# HD-JYQ70-YD03-POWER.net
KiCad netlist of a schematic drawn in Altium Designer
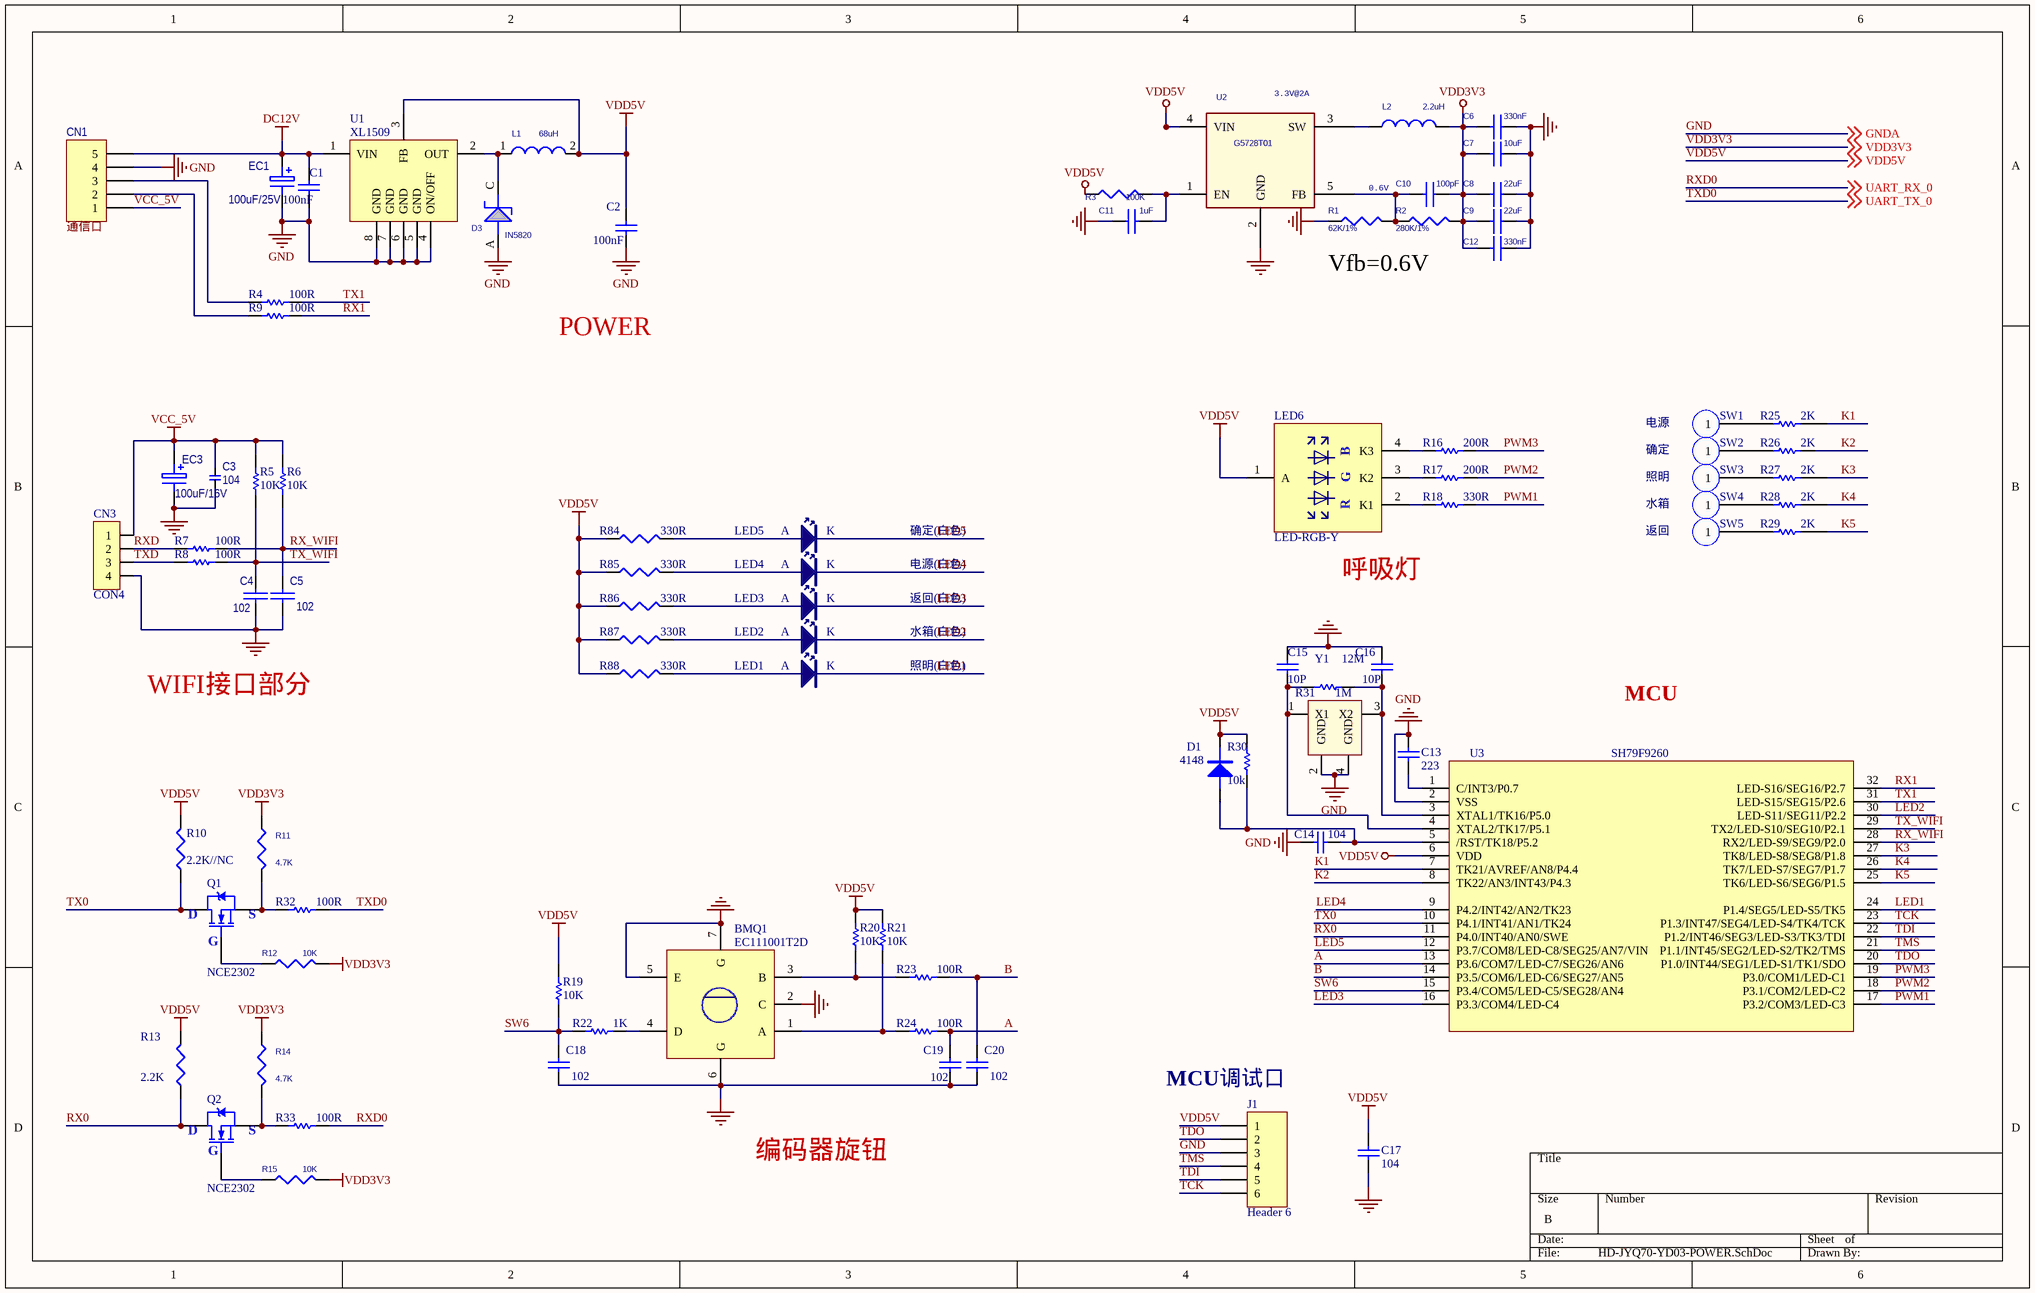
[diagram p0: HD-JYQ70-YD03-POWER.SchDoc]

(export (version "E")
  (design (tool "Eeschema 10.0.6"))
  (components
    (comp (ref "BMQ1")
      (value "EC111001T2D")
      (footprint "EC111001T2D")
      (libsource (lib "DHX") (part "EC111001T2D"))
    )
    (comp (ref "C1")
      (value "100nF")
      (footprint "X-0603C")
      (description "Capacitor (Semiconductor SIM Model)")
      (fields (field (name "Comment") "Cap Semi") (field (name "PUBLISHER") "Altium Limited"))
      (libsource (lib "Miscellaneous Devices") (part "Cap Semi"))
    )
    (comp (ref "C2")
      (value "100nF")
      (footprint "X-0603C")
      (description "Capacitor (Semiconductor SIM Model)")
      (fields (field (name "Comment") "Cap Semi") (field (name "PUBLISHER") "Altium Limited"))
      (libsource (lib "Miscellaneous Devices") (part "Cap Semi"))
    )
    (comp (ref "C3")
      (value "104")
      (footprint "X-0603C")
      (description "贴片电容")
      (libsource (lib "*") (part "C1"))
    )
    (comp (ref "C4")
      (value "102")
      (footprint "X-0603C")
      (description "贴片电容")
      (libsource (lib "*") (part "CAP1"))
    )
    (comp (ref "C5")
      (value "102")
      (footprint "X-0603C")
      (description "贴片电容")
      (libsource (lib "*") (part "CAP1"))
    )
    (comp (ref "C6")
      (value "330nF")
      (footprint "X-0603C")
      (fields (field (name "VOLTAGE") "X5R/10V"))
      (libsource (lib "*") (part "CAP NP_0"))
    )
    (comp (ref "C7")
      (value "10uF")
      (footprint "X-0805C")
      (fields (field (name "VOLTAGE") "X5R/6.3V"))
      (libsource (lib "*") (part "CAP NP"))
    )
    (comp (ref "C8")
      (value "22uF")
      (footprint "X-0805C")
      (fields (field (name "VOLTAGE") "X5R/6.3V"))
      (libsource (lib "*") (part "CAP NP"))
    )
    (comp (ref "C9")
      (value "22uF")
      (footprint "X-0805C")
      (fields (field (name "VOLTAGE") "X5R/6.3V"))
      (libsource (lib "*") (part "CAP NP"))
    )
    (comp (ref "C10")
      (value "100pF")
      (footprint "X-0603C")
      (fields (field (name "VOLTAGE") "COG/5V"))
      (libsource (lib "*") (part "CAP NP"))
    )
    (comp (ref "C11")
      (value "1uF")
      (footprint "X-0603C")
      (fields (field (name "VOLTAGE") "X5R/10V"))
      (libsource (lib "*") (part "CAP NP_0"))
    )
    (comp (ref "C12")
      (value "330nF")
      (footprint "X-0805C")
      (fields (field (name "VOLTAGE") "X5R/10V"))
      (libsource (lib "*") (part "CAP NP"))
    )
    (comp (ref "C13")
      (value "223")
      (footprint "X-0603C")
      (description "Capacitor")
      (fields (field (name "Comment") "Cap") (field (name "PUBLISHER") "Altium Limited"))
      (libsource (lib "Miscellaneous Devices") (part "Cap"))
    )
    (comp (ref "C14")
      (value "104")
      (footprint "X-0603C")
      (description "Capacitor")
      (fields (field (name "Comment") "Cap") (field (name "PUBLISHER") "Altium Limited"))
      (libsource (lib "Miscellaneous Devices") (part "Cap"))
    )
    (comp (ref "C15")
      (value "10P")
      (footprint "X-0603C")
      (description "Capacitor")
      (fields (field (name "Comment") "Cap") (field (name "PUBLISHER") "Altium Limited"))
      (libsource (lib "Miscellaneous Devices") (part "Cap"))
    )
    (comp (ref "C16")
      (value "10P")
      (footprint "X-0603C")
      (description "Capacitor")
      (fields (field (name "Comment") "Cap") (field (name "PUBLISHER") "Altium Limited"))
      (libsource (lib "Miscellaneous Devices") (part "Cap"))
    )
    (comp (ref "C17")
      (value "104")
      (footprint "X-0603C")
      (description "Capacitor")
      (fields (field (name "Comment") "Cap") (field (name "PUBLISHER") "Altium Limited"))
      (libsource (lib "Miscellaneous Devices") (part "Cap"))
    )
    (comp (ref "C18")
      (value "102")
      (footprint "X-0603C")
      (description "Capacitor")
      (fields (field (name "Comment") "Cap") (field (name "PUBLISHER") "Altium Limited"))
      (libsource (lib "Miscellaneous Devices") (part "Cap"))
    )
    (comp (ref "C19")
      (value "102")
      (footprint "X-0603C")
      (description "Capacitor")
      (fields (field (name "Comment") "Cap") (field (name "PUBLISHER") "Altium Limited"))
      (libsource (lib "Miscellaneous Devices") (part "Cap"))
    )
    (comp (ref "C20")
      (value "102")
      (footprint "X-0603C")
      (description "Capacitor")
      (fields (field (name "Comment") "Cap") (field (name "PUBLISHER") "Altium Limited"))
      (libsource (lib "Miscellaneous Devices") (part "Cap"))
    )
    (comp (ref "CN1")
      (value "通信口")
      (footprint "JC25-5Y")
      (description "孔座")
      (fields (field (name "PUBLISHER") "Altium Limited"))
      (libsource (lib "Miscellaneous Connectors") (part "Header 5"))
    )
    (comp (ref "CN3")
      (value "CON4")
      (footprint "CoN-JC25-4Y")
      (description "Connector")
      (libsource (lib "Stander PCB lib_V1.2(20170627)") (part "CON4"))
    )
    (comp (ref "D1") (value "4148") (footprint "H-DIODE_SMA") (libsource (lib "*") (part "DIODE")))
    (comp (ref "D3")
      (value "IN5820")
      (footprint "DO-214AC")
      (libsource (lib "E663AHE_TFT") (part "DIODE ZENER_0"))
    )
    (comp (ref "EC1")
      (value "100uF/25V")
      (footprint "C6*8*6")
      (description "电解电容")
      (libsource (lib "*") (part "EC"))
    )
    (comp (ref "EC3")
      (value "100uF/16V")
      (footprint "C6*8*6")
      (description "电解电容")
      (libsource (lib "*") (part "EC"))
    )
    (comp (ref "J1")
      (value "Header 6")
      (footprint "CON_TJC8-6A")
      (description "Header, 6-Pin")
      (fields (field (name "PUBLISHER") "Altium Limited"))
      (libsource (lib "Miscellaneous Connectors") (part "Header 6"))
    )
    (comp (ref "L1")
      (value "68uH")
      (footprint "ZAD-6045")
      (libsource (lib "E663AHE_TFT") (part "L_SMD_15uH_3.2A"))
    )
    (comp (ref "L2") (value "2.2uH") (footprint "ZAD-4030") (libsource (lib "*") (part "INDUCTOR_0")))
    (comp (ref "LED1") (value "~") (footprint "LED2P-5MM") (libsource (lib "nie") (part "LED")))
    (comp (ref "LED2") (value "~") (footprint "LED2P-5MM") (libsource (lib "nie") (part "LED")))
    (comp (ref "LED3") (value "~") (footprint "LED2P-5MM") (libsource (lib "nie") (part "LED")))
    (comp (ref "LED4") (value "~") (footprint "LED2P-5MM") (libsource (lib "nie") (part "LED")))
    (comp (ref "LED5") (value "~") (footprint "LED2P-5MM") (libsource (lib "nie") (part "LED")))
    (comp (ref "LED6") (value "LED-RGB-Y") (footprint "LED-RGB-Y") (libsource (lib "DHX") (part "LED-RGB-Y")))
    (comp (ref "Q1")
      (value "NCE2302")
      (footprint "X-SOT23")
      (description "N-Channel Power MOSFET")
      (fields (field (name "PUBLISHER") "Altium Limited"))
      (libsource (lib "Miscellaneous Devices") (part "NMOS-2"))
    )
    (comp (ref "Q2")
      (value "NCE2302")
      (footprint "X-SOT23")
      (description "N-Channel Power MOSFET")
      (fields (field (name "PUBLISHER") "Altium Limited"))
      (libsource (lib "Miscellaneous Devices") (part "NMOS-2"))
    )
    (comp (ref "R1") (value "62K/1%") (footprint "X-0603R") (libsource (lib "*") (part "R")))
    (comp (ref "R2") (value "280K/1%") (footprint "X-0603R") (libsource (lib "*") (part "R")))
    (comp (ref "R3") (value "100K") (footprint "X-0603R") (libsource (lib "*") (part "R")))
    (comp (ref "R4")
      (value "100R")
      (footprint "X-0603R")
      (description "Resistor")
      (fields (field (name "Comment") "Res1") (field (name "PUBLISHER") "Altium Limited"))
      (libsource (lib "Miscellaneous Devices") (part "Res1"))
    )
    (comp (ref "R5")
      (value "10K")
      (footprint "X-0603R")
      (description "Resistor")
      (fields (field (name "Comment") "Res1") (field (name "PUBLISHER") "Altium Limited"))
      (libsource (lib "Miscellaneous Devices") (part "Res1"))
    )
    (comp (ref "R6")
      (value "10K")
      (footprint "X-0603R")
      (description "Resistor")
      (fields (field (name "Comment") "Res1") (field (name "PUBLISHER") "Altium Limited"))
      (libsource (lib "Miscellaneous Devices") (part "Res1"))
    )
    (comp (ref "R7")
      (value "100R")
      (footprint "X-0603R")
      (description "Resistor")
      (fields (field (name "Comment") "Res1") (field (name "PUBLISHER") "Altium Limited"))
      (libsource (lib "Miscellaneous Devices") (part "Res1"))
    )
    (comp (ref "R8")
      (value "100R")
      (footprint "X-0603R")
      (description "Resistor")
      (fields (field (name "Comment") "Res1") (field (name "PUBLISHER") "Altium Limited"))
      (libsource (lib "Miscellaneous Devices") (part "Res1"))
    )
    (comp (ref "R9")
      (value "100R")
      (footprint "X-0603R")
      (description "Resistor")
      (fields (field (name "Comment") "Res1") (field (name "PUBLISHER") "Altium Limited"))
      (libsource (lib "Miscellaneous Devices") (part "Res1"))
    )
    (comp (ref "R10")
      (value "2.2K//NC")
      (footprint "X-0603R")
      (description "Resistor")
      (fields (field (name "Comment") "2.2K") (field (name "PUBLISHER") "Altium Limited"))
      (libsource (lib "Miscellaneous Devices") (part "Res3"))
    )
    (comp (ref "R11") (value "4.7K") (footprint "X-0603R") (libsource (lib "*") (part "R_Dup4")))
    (comp (ref "R12") (value "10K") (footprint "X-0603R") (libsource (lib "*") (part "R_Dup4")))
    (comp (ref "R13")
      (value "2.2K")
      (footprint "X-0603R")
      (description "Resistor")
      (fields (field (name "PUBLISHER") "Altium Limited"))
      (libsource (lib "Miscellaneous Devices") (part "Res3"))
    )
    (comp (ref "R14") (value "4.7K") (footprint "X-0603R") (libsource (lib "*") (part "R_Dup4")))
    (comp (ref "R15") (value "10K") (footprint "X-0603R") (libsource (lib "*") (part "R_Dup4")))
    (comp (ref "R16")
      (value "200R")
      (footprint "X-0603R")
      (description "Resistor")
      (fields (field (name "Comment") "Res1") (field (name "PUBLISHER") "Altium Limited"))
      (libsource (lib "Miscellaneous Devices") (part "Res1"))
    )
    (comp (ref "R17")
      (value "200R")
      (footprint "X-0603R")
      (description "Resistor")
      (fields (field (name "Comment") "Res1") (field (name "PUBLISHER") "Altium Limited"))
      (libsource (lib "Miscellaneous Devices") (part "Res1"))
    )
    (comp (ref "R18")
      (value "330R")
      (footprint "X-0603R")
      (description "Resistor")
      (fields (field (name "Comment") "Res1") (field (name "PUBLISHER") "Altium Limited"))
      (libsource (lib "Miscellaneous Devices") (part "Res1"))
    )
    (comp (ref "R19")
      (value "10K")
      (footprint "X-0603R")
      (description "Resistor")
      (fields (field (name "Comment") "Res1") (field (name "PUBLISHER") "Altium Limited"))
      (libsource (lib "Miscellaneous Devices") (part "Res1"))
    )
    (comp (ref "R20")
      (value "10K")
      (footprint "X-0603R")
      (description "Resistor")
      (fields (field (name "Comment") "Res1") (field (name "PUBLISHER") "Altium Limited"))
      (libsource (lib "Miscellaneous Devices") (part "Res1"))
    )
    (comp (ref "R21")
      (value "10K")
      (footprint "X-0603R")
      (description "Resistor")
      (fields (field (name "Comment") "Res1") (field (name "PUBLISHER") "Altium Limited"))
      (libsource (lib "Miscellaneous Devices") (part "Res1"))
    )
    (comp (ref "R22")
      (value "1K")
      (footprint "X-0603R")
      (description "Resistor")
      (fields (field (name "Comment") "Res1") (field (name "PUBLISHER") "Altium Limited"))
      (libsource (lib "Miscellaneous Devices") (part "Res1"))
    )
    (comp (ref "R23")
      (value "100R")
      (footprint "X-0603R")
      (description "Resistor")
      (fields (field (name "Comment") "Res1") (field (name "PUBLISHER") "Altium Limited"))
      (libsource (lib "Miscellaneous Devices") (part "Res1"))
    )
    (comp (ref "R24")
      (value "100R")
      (footprint "X-0603R")
      (description "Resistor")
      (fields (field (name "Comment") "Res1") (field (name "PUBLISHER") "Altium Limited"))
      (libsource (lib "Miscellaneous Devices") (part "Res1"))
    )
    (comp (ref "R25")
      (value "2K")
      (footprint "X-0603R")
      (description "Resistor")
      (fields (field (name "Comment") "Res1") (field (name "PUBLISHER") "Altium Limited"))
      (libsource (lib "Miscellaneous Devices") (part "Res1"))
    )
    (comp (ref "R26")
      (value "2K")
      (footprint "X-0603R")
      (description "Resistor")
      (fields (field (name "Comment") "Res1") (field (name "PUBLISHER") "Altium Limited"))
      (libsource (lib "Miscellaneous Devices") (part "Res1"))
    )
    (comp (ref "R27")
      (value "2K")
      (footprint "X-0603R")
      (description "Resistor")
      (fields (field (name "Comment") "Res1") (field (name "PUBLISHER") "Altium Limited"))
      (libsource (lib "Miscellaneous Devices") (part "Res1"))
    )
    (comp (ref "R28")
      (value "2K")
      (footprint "X-0603R")
      (description "Resistor")
      (fields (field (name "Comment") "Res1") (field (name "PUBLISHER") "Altium Limited"))
      (libsource (lib "Miscellaneous Devices") (part "Res1"))
    )
    (comp (ref "R29")
      (value "2K")
      (footprint "X-0603R")
      (description "Resistor")
      (fields (field (name "Comment") "Res1") (field (name "PUBLISHER") "Altium Limited"))
      (libsource (lib "Miscellaneous Devices") (part "Res1"))
    )
    (comp (ref "R30")
      (value "10k")
      (footprint "X-0603R")
      (description "Resistor")
      (fields (field (name "Comment") "Res1") (field (name "PUBLISHER") "Altium Limited"))
      (libsource (lib "Miscellaneous Devices") (part "Res1"))
    )
    (comp (ref "R31")
      (value "1M")
      (footprint "X-0603R")
      (description "Resistor")
      (fields (field (name "Comment") "Res1") (field (name "PUBLISHER") "Altium Limited"))
      (libsource (lib "Miscellaneous Devices") (part "Res1"))
    )
    (comp (ref "R32")
      (value "100R")
      (footprint "X-0603R")
      (description "Resistor")
      (fields (field (name "Comment") "Res1") (field (name "PUBLISHER") "Altium Limited"))
      (libsource (lib "Miscellaneous Devices") (part "Res1"))
    )
    (comp (ref "R33")
      (value "100R")
      (footprint "X-0603R")
      (description "Resistor")
      (fields (field (name "Comment") "Res1") (field (name "PUBLISHER") "Altium Limited"))
      (libsource (lib "Miscellaneous Devices") (part "Res1"))
    )
    (comp (ref "R84")
      (value "330R")
      (footprint "X-0603R")
      (description "Resistor")
      (fields (field (name "Comment") "10K") (field (name "PUBLISHER") "Altium Limited"))
      (libsource (lib "Miscellaneous Devices") (part "Res3"))
    )
    (comp (ref "R85")
      (value "330R")
      (footprint "X-0603R")
      (description "Resistor")
      (fields (field (name "Comment") "10K") (field (name "PUBLISHER") "Altium Limited"))
      (libsource (lib "Miscellaneous Devices") (part "Res3"))
    )
    (comp (ref "R86")
      (value "330R")
      (footprint "X-0603R")
      (description "Resistor")
      (fields (field (name "Comment") "10K") (field (name "PUBLISHER") "Altium Limited"))
      (libsource (lib "Miscellaneous Devices") (part "Res3"))
    )
    (comp (ref "R87")
      (value "330R")
      (footprint "X-0603R")
      (description "Resistor")
      (fields (field (name "Comment") "10K") (field (name "PUBLISHER") "Altium Limited"))
      (libsource (lib "Miscellaneous Devices") (part "Res3"))
    )
    (comp (ref "R88")
      (value "330R")
      (footprint "X-0603R")
      (description "Resistor")
      (fields (field (name "Comment") "10K") (field (name "PUBLISHER") "Altium Limited"))
      (libsource (lib "Miscellaneous Devices") (part "Res3"))
    )
    (comp (ref "SW1") (value "返回") (footprint "SW-14") (libsource (lib "*") (part "SW")))
    (comp (ref "SW2") (value "确定") (footprint "SW-14") (libsource (lib "*") (part "SW")))
    (comp (ref "SW3") (value "电源") (footprint "SW-14") (libsource (lib "*") (part "SW")))
    (comp (ref "SW4") (value "水箱") (footprint "SW-14") (libsource (lib "*") (part "SW")))
    (comp (ref "SW5") (value "照明") (footprint "SW-14") (libsource (lib "*") (part "SW")))
    (comp (ref "U1") (value "XL1509") (footprint "X-SOP8-50-150") (libsource (lib "DHX") (part "XL1509")))
    (comp (ref "U2")
      (value "G5728T01")
      (footprint "TSOT25-5P$2F$0.95$2F$3X3")
      (libsource (lib "*") (part "05. IT7831TS_TSOT25"))
    )
    (comp (ref "U3")
      (value "SH79F9260")
      (footprint "X-QFP32-080-0707L")
      (libsource (lib "DHX") (part "SH79F9260"))
    )
    (comp (ref "Y1") (value "12M") (footprint "CRYSTALS-SMD-320X250") (libsource (lib "FYK") (part "3225")))
  )
  (nets
    (net (code "1") (name "/A") (class "Default")
      (node (ref "C19") (pin "2") (pinfunction "2_2") (pintype "passive"))
      (node (ref "R24") (pin "2") (pinfunction "2_2") (pintype "passive"))
      (node (ref "U3") (pin "13") (pinfunction "P3.6/COM7/LED-C7/SEG26/AN6_13") (pintype "passive"))
    )
    (net (code "2") (name "/B") (class "Default")
      (node (ref "C20") (pin "2") (pinfunction "2_2") (pintype "passive"))
      (node (ref "R23") (pin "2") (pinfunction "2_2") (pintype "passive"))
      (node (ref "U3") (pin "14") (pinfunction "P3.5/COM6/LED-C6/SEG27/AN5_14") (pintype "passive"))
    )
    (net (code "3") (name "/K1") (class "Default")
      (node (ref "R25") (pin "2") (pinfunction "2_2") (pintype "passive"))
      (node (ref "U3") (pin "7") (pinfunction "TK21/AVREF/AN8/P4.4_7") (pintype "passive"))
    )
    (net (code "4") (name "/K2") (class "Default")
      (node (ref "R26") (pin "2") (pinfunction "2_2") (pintype "passive"))
      (node (ref "U3") (pin "8") (pinfunction "TK22/AN3/INT43/P4.3_8") (pintype "passive"))
    )
    (net (code "5") (name "/K3") (class "Default")
      (node (ref "R27") (pin "2") (pinfunction "2_2") (pintype "passive"))
      (node (ref "U3") (pin "27") (pinfunction "TK8/LED-S8/SEG8/P1.8_27") (pintype "passive"))
    )
    (net (code "6") (name "/K4") (class "Default")
      (node (ref "R28") (pin "2") (pinfunction "2_2") (pintype "passive"))
      (node (ref "U3") (pin "26") (pinfunction "TK7/LED-S7/SEG7/P1.7_26") (pintype "passive"))
    )
    (net (code "7") (name "/K5") (class "Default")
      (node (ref "R29") (pin "2") (pinfunction "2_2") (pintype "passive"))
      (node (ref "U3") (pin "25") (pinfunction "TK6/LED-S6/SEG6/P1.5_25") (pintype "passive"))
    )
    (net (code "8") (name "/LED1") (class "Default")
      (node (ref "LED1") (pin "K") (pinfunction "K_K") (pintype "passive"))
      (node (ref "U3") (pin "24") (pinfunction "P1.4/SEG5/LED-S5/TK5_24") (pintype "passive"))
    )
    (net (code "9") (name "/LED2") (class "Default")
      (node (ref "LED2") (pin "K") (pinfunction "K_K") (pintype "passive"))
      (node (ref "U3") (pin "30") (pinfunction "LED-S11/SEG11/P2.2_30") (pintype "passive"))
    )
    (net (code "10") (name "/LED3") (class "Default")
      (node (ref "LED3") (pin "K") (pinfunction "K_K") (pintype "passive"))
      (node (ref "U3") (pin "16") (pinfunction "P3.3/COM4/LED-C4_16") (pintype "passive"))
    )
    (net (code "11") (name "/LED4") (class "Default")
      (node (ref "LED4") (pin "K") (pinfunction "K_K") (pintype "passive"))
      (node (ref "U3") (pin "9") (pinfunction "P4.2/INT42/AN2/TK23_9") (pintype "passive"))
    )
    (net (code "12") (name "/LED5") (class "Default")
      (node (ref "LED5") (pin "K") (pinfunction "K_K") (pintype "passive"))
      (node (ref "U3") (pin "12") (pinfunction "P3.7/COM8/LED-C8/SEG25/AN7/VIN_12") (pintype "passive"))
    )
    (net (code "13") (name "/PWM1") (class "Default")
      (node (ref "R18") (pin "2") (pinfunction "2_2") (pintype "passive"))
      (node (ref "U3") (pin "17") (pinfunction "P3.2/COM3/LED-C3_17") (pintype "passive"))
    )
    (net (code "14") (name "/PWM2") (class "Default")
      (node (ref "R17") (pin "2") (pinfunction "2_2") (pintype "passive"))
      (node (ref "U3") (pin "18") (pinfunction "P3.1/COM2/LED-C2_18") (pintype "passive"))
    )
    (net (code "15") (name "/PWM3") (class "Default")
      (node (ref "R16") (pin "2") (pinfunction "2_2") (pintype "passive"))
      (node (ref "U3") (pin "19") (pinfunction "P3.0/COM1/LED-C1_19") (pintype "passive"))
    )
    (net (code "16") (name "/RX0") (class "Default")
      (node (ref "Q2") (pin "2") (pinfunction "D_2") (pintype "passive"))
      (node (ref "R13") (pin "1") (pinfunction "1_1") (pintype "passive"))
      (node (ref "U3") (pin "11") (pinfunction "P4.0/INT40/AN0/SWE_11") (pintype "passive"))
    )
    (net (code "17") (name "/RX1") (class "Default")
      (node (ref "R9") (pin "2") (pinfunction "2_2") (pintype "passive"))
      (node (ref "U3") (pin "32") (pinfunction "LED-S16/SEG16/P2.7_32") (pintype "passive"))
    )
    (net (code "18") (name "/RXD") (class "Default")
      (node (ref "CN3") (pin "2") (pinfunction "2_2") (pintype "passive"))
      (node (ref "R7") (pin "1") (pinfunction "1_1") (pintype "passive"))
    )
    (net (code "19") (name "/RX_WIFI") (class "Default")
      (node (ref "C5") (pin "2") (pinfunction "2_2") (pintype "passive"))
      (node (ref "R6") (pin "1") (pinfunction "1_1") (pintype "passive"))
      (node (ref "R7") (pin "2") (pinfunction "2_2") (pintype "passive"))
      (node (ref "U3") (pin "28") (pinfunction "RX2/LED-S9/SEG9/P2.0_28") (pintype "passive"))
    )
    (net (code "20") (name "/SW6") (class "Default")
      (node (ref "C18") (pin "2") (pinfunction "2_2") (pintype "passive"))
      (node (ref "R19") (pin "1") (pinfunction "1_1") (pintype "passive"))
      (node (ref "R22") (pin "1") (pinfunction "1_1") (pintype "passive"))
      (node (ref "U3") (pin "15") (pinfunction "P3.4/COM5/LED-C5/SEG28/AN4_15") (pintype "passive"))
    )
    (net (code "21") (name "/TCK") (class "Default")
      (node (ref "J1") (pin "6") (pinfunction "6_6") (pintype "passive"))
      (node (ref "U3") (pin "23") (pinfunction "P1.3/INT47/SEG4/LED-S4/TK4/TCK_23") (pintype "passive"))
    )
    (net (code "22") (name "/TDI") (class "Default")
      (node (ref "J1") (pin "5") (pinfunction "5_5") (pintype "passive"))
      (node (ref "U3") (pin "22") (pinfunction "P1.2/INT46/SEG3/LED-S3/TK3/TDI_22") (pintype "passive"))
    )
    (net (code "23") (name "/TDO") (class "Default")
      (node (ref "J1") (pin "2") (pinfunction "2_2") (pintype "passive"))
      (node (ref "U3") (pin "20") (pinfunction "P1.0/INT44/SEG1/LED-S1/TK1/SDO_20") (pintype "passive"))
    )
    (net (code "24") (name "/TMS") (class "Default")
      (node (ref "J1") (pin "4") (pinfunction "4_4") (pintype "passive"))
      (node (ref "U3") (pin "21") (pinfunction "P1.1/INT45/SEG2/LED-S2/TK2/TMS_21") (pintype "passive"))
    )
    (net (code "25") (name "/TX0") (class "Default")
      (node (ref "Q1") (pin "2") (pinfunction "D_2") (pintype "passive"))
      (node (ref "R10") (pin "1") (pinfunction "1_1") (pintype "passive"))
      (node (ref "U3") (pin "10") (pinfunction "P4.1/INT41/AN1/TK24_10") (pintype "passive"))
    )
    (net (code "26") (name "/TX1") (class "Default")
      (node (ref "R4") (pin "2") (pinfunction "2_2") (pintype "passive"))
      (node (ref "U3") (pin "31") (pinfunction "LED-S15/SEG15/P2.6_31") (pintype "passive"))
    )
    (net (code "27") (name "/TXD") (class "Default")
      (node (ref "CN3") (pin "3") (pinfunction "3_3") (pintype "passive"))
      (node (ref "R8") (pin "1") (pinfunction "1_1") (pintype "passive"))
    )
    (net (code "28") (name "/TX_WIFI") (class "Default")
      (node (ref "C4") (pin "2") (pinfunction "2_2") (pintype "passive"))
      (node (ref "R5") (pin "1") (pinfunction "1_1") (pintype "passive"))
      (node (ref "R8") (pin "2") (pinfunction "2_2") (pintype "passive"))
      (node (ref "U3") (pin "29") (pinfunction "TX2/LED-S10/SEG10/P2.1_29") (pintype "passive"))
    )
    (net (code "29") (name "DC12V") (class "Default")
      (node (ref "C1") (pin "2") (pinfunction "2_2") (pintype "passive"))
      (node (ref "CN1") (pin "5") (pinfunction "5_5") (pintype "passive"))
      (node (ref "EC1") (pin "1") (pinfunction "1_1") (pintype "passive"))
      (node (ref "U1") (pin "1") (pinfunction "VIN_1") (pintype "passive"))
    )
    (net (code "30") (name "GND") (class "Default")
      (node (ref "BMQ1") (pin "2") (pinfunction "C_2") (pintype "passive"))
      (node (ref "BMQ1") (pin "5") (pinfunction "E_5") (pintype "passive"))
      (node (ref "BMQ1") (pin "6") (pinfunction "G_6") (pintype "passive"))
      (node (ref "BMQ1") (pin "7") (pinfunction "G_7") (pintype "passive"))
      (node (ref "C1") (pin "1") (pinfunction "1_1") (pintype "passive"))
      (node (ref "C11") (pin "1") (pinfunction "1_1") (pintype "passive"))
      (node (ref "C12") (pin "1") (pinfunction "1_1") (pintype "passive"))
      (node (ref "C13") (pin "2") (pinfunction "2_2") (pintype "passive"))
      (node (ref "C14") (pin "1") (pinfunction "1_1") (pintype "passive"))
      (node (ref "C15") (pin "2") (pinfunction "2_2") (pintype "passive"))
      (node (ref "C16") (pin "2") (pinfunction "2_2") (pintype "passive"))
      (node (ref "C17") (pin "1") (pinfunction "1_1") (pintype "passive"))
      (node (ref "C18") (pin "1") (pinfunction "1_1") (pintype "passive"))
      (node (ref "C19") (pin "1") (pinfunction "1_1") (pintype "passive"))
      (node (ref "C2") (pin "1") (pinfunction "1_1") (pintype "passive"))
      (node (ref "C20") (pin "1") (pinfunction "1_1") (pintype "passive"))
      (node (ref "C3") (pin "2") (pinfunction "2_2") (pintype "passive"))
      (node (ref "C4") (pin "1") (pinfunction "1_1") (pintype "passive"))
      (node (ref "C5") (pin "1") (pinfunction "1_1") (pintype "passive"))
      (node (ref "C6") (pin "1") (pinfunction "1_1") (pintype "passive"))
      (node (ref "C7") (pin "1") (pinfunction "1_1") (pintype "passive"))
      (node (ref "C8") (pin "1") (pinfunction "1_1") (pintype "passive"))
      (node (ref "C9") (pin "1") (pinfunction "1_1") (pintype "passive"))
      (node (ref "CN1") (pin "4") (pinfunction "4_4") (pintype "passive"))
      (node (ref "CN3") (pin "4") (pinfunction "4_4") (pintype "passive"))
      (node (ref "D3") (pin "A") (pinfunction "ANODE_A") (pintype "passive"))
      (node (ref "EC1") (pin "2") (pinfunction "2_2") (pintype "passive"))
      (node (ref "EC3") (pin "2") (pinfunction "2_2") (pintype "passive"))
      (node (ref "J1") (pin "3") (pinfunction "3_3") (pintype "passive"))
      (node (ref "R1") (pin "1") (pinfunction "1_1") (pintype "passive"))
      (node (ref "U1") (pin "4") (pinfunction "ON/OFF_4") (pintype "passive"))
      (node (ref "U1") (pin "5") (pinfunction "GND_5") (pintype "passive"))
      (node (ref "U1") (pin "6") (pinfunction "GND_6") (pintype "passive"))
      (node (ref "U1") (pin "7") (pinfunction "GND_7") (pintype "passive"))
      (node (ref "U1") (pin "8") (pinfunction "GND_8") (pintype "passive"))
      (node (ref "U2") (pin "2") (pinfunction "GND_2") (pintype "passive"))
      (node (ref "U3") (pin "2") (pinfunction "VSS_2") (pintype "passive"))
      (node (ref "Y1") (pin "2") (pinfunction "GND_2") (pintype "passive"))
      (node (ref "Y1") (pin "4") (pinfunction "GND_4") (pintype "passive"))
    )
    (net (code "31") (name "Net-(BMQ1-A)") (class "Default")
      (node (ref "BMQ1") (pin "1") (pinfunction "A_1") (pintype "passive"))
      (node (ref "R21") (pin "1") (pinfunction "1_1") (pintype "passive"))
      (node (ref "R24") (pin "1") (pinfunction "1_1") (pintype "passive"))
    )
    (net (code "32") (name "Net-(BMQ1-B)") (class "Default")
      (node (ref "BMQ1") (pin "3") (pinfunction "B_3") (pintype "passive"))
      (node (ref "R20") (pin "1") (pinfunction "1_1") (pintype "passive"))
      (node (ref "R23") (pin "1") (pinfunction "1_1") (pintype "passive"))
    )
    (net (code "33") (name "Net-(BMQ1-D)") (class "Default")
      (node (ref "BMQ1") (pin "4") (pinfunction "D_4") (pintype "passive"))
      (node (ref "R22") (pin "2") (pinfunction "2_2") (pintype "passive"))
    )
    (net (code "34") (name "Net-(CN1-Pad2)") (class "Default")
      (node (ref "CN1") (pin "2") (pinfunction "2_2") (pintype "passive"))
      (node (ref "R9") (pin "1") (pinfunction "1_1") (pintype "passive"))
    )
    (net (code "35") (name "Net-(CN1-Pad3)") (class "Default")
      (node (ref "CN1") (pin "3") (pinfunction "3_3") (pintype "passive"))
      (node (ref "R4") (pin "1") (pinfunction "1_1") (pintype "passive"))
    )
    (net (code "36") (name "Net-(D1-A)") (class "Default")
      (node (ref "C14") (pin "2") (pinfunction "2_2") (pintype "passive"))
      (node (ref "D1") (pin "1") (pinfunction "A_1") (pintype "passive"))
      (node (ref "R30") (pin "1") (pinfunction "1_1") (pintype "passive"))
      (node (ref "U3") (pin "5") (pinfunction "/RST/TK18/P5.2_5") (pintype "passive"))
    )
    (net (code "37") (name "Net-(D3-CATHODE)") (class "Default")
      (node (ref "D3") (pin "C") (pinfunction "CATHODE_C") (pintype "passive"))
      (node (ref "L1") (pin "1") (pinfunction "1_1") (pintype "passive"))
      (node (ref "U1") (pin "2") (pinfunction "OUT_2") (pintype "passive"))
    )
    (net (code "38") (name "Net-(LED1-PadA)") (class "Default")
      (node (ref "LED1") (pin "A") (pinfunction "A_A") (pintype "passive"))
      (node (ref "R88") (pin "2") (pinfunction "2_2") (pintype "passive"))
    )
    (net (code "39") (name "Net-(LED2-PadA)") (class "Default")
      (node (ref "LED2") (pin "A") (pinfunction "A_A") (pintype "passive"))
      (node (ref "R87") (pin "2") (pinfunction "2_2") (pintype "passive"))
    )
    (net (code "40") (name "Net-(LED3-PadA)") (class "Default")
      (node (ref "LED3") (pin "A") (pinfunction "A_A") (pintype "passive"))
      (node (ref "R86") (pin "2") (pinfunction "2_2") (pintype "passive"))
    )
    (net (code "41") (name "Net-(LED4-PadA)") (class "Default")
      (node (ref "LED4") (pin "A") (pinfunction "A_A") (pintype "passive"))
      (node (ref "R85") (pin "2") (pinfunction "2_2") (pintype "passive"))
    )
    (net (code "42") (name "Net-(LED5-PadA)") (class "Default")
      (node (ref "LED5") (pin "A") (pinfunction "A_A") (pintype "passive"))
      (node (ref "R84") (pin "2") (pinfunction "2_2") (pintype "passive"))
    )
    (net (code "43") (name "Net-(LED6-K1)") (class "Default")
      (node (ref "LED6") (pin "2") (pinfunction "K1_2") (pintype "passive"))
      (node (ref "R18") (pin "1") (pinfunction "1_1") (pintype "passive"))
    )
    (net (code "44") (name "Net-(LED6-K2)") (class "Default")
      (node (ref "LED6") (pin "3") (pinfunction "K2_3") (pintype "passive"))
      (node (ref "R17") (pin "1") (pinfunction "1_1") (pintype "passive"))
    )
    (net (code "45") (name "Net-(LED6-K3)") (class "Default")
      (node (ref "LED6") (pin "4") (pinfunction "K3_4") (pintype "passive"))
      (node (ref "R16") (pin "1") (pinfunction "1_1") (pintype "passive"))
    )
    (net (code "46") (name "Net-(Q1-G)") (class "Default")
      (node (ref "Q1") (pin "1") (pinfunction "G_1") (pintype "passive"))
      (node (ref "R12") (pin "1") (pinfunction "1_1") (pintype "passive"))
    )
    (net (code "47") (name "Net-(Q1-S)") (class "Default")
      (node (ref "Q1") (pin "3") (pinfunction "S_3") (pintype "passive"))
      (node (ref "R11") (pin "2") (pinfunction "2_2") (pintype "passive"))
      (node (ref "R32") (pin "1") (pinfunction "1_1") (pintype "passive"))
    )
    (net (code "48") (name "Net-(Q2-G)") (class "Default")
      (node (ref "Q2") (pin "1") (pinfunction "G_1") (pintype "passive"))
      (node (ref "R15") (pin "1") (pinfunction "1_1") (pintype "passive"))
    )
    (net (code "49") (name "Net-(Q2-S)") (class "Default")
      (node (ref "Q2") (pin "3") (pinfunction "S_3") (pintype "passive"))
      (node (ref "R14") (pin "2") (pinfunction "2_2") (pintype "passive"))
      (node (ref "R33") (pin "1") (pinfunction "1_1") (pintype "passive"))
    )
    (net (code "50") (name "Net-(R25-Pad1)") (class "Default")
      (node (ref "R25") (pin "1") (pinfunction "1_1") (pintype "passive"))
      (node (ref "SW1") (pin "1") (pinfunction "1_1") (pintype "passive"))
    )
    (net (code "51") (name "Net-(R26-Pad1)") (class "Default")
      (node (ref "R26") (pin "1") (pinfunction "1_1") (pintype "passive"))
      (node (ref "SW2") (pin "1") (pinfunction "1_1") (pintype "passive"))
    )
    (net (code "52") (name "Net-(R27-Pad1)") (class "Default")
      (node (ref "R27") (pin "1") (pinfunction "1_1") (pintype "passive"))
      (node (ref "SW3") (pin "1") (pinfunction "1_1") (pintype "passive"))
    )
    (net (code "53") (name "Net-(R28-Pad1)") (class "Default")
      (node (ref "R28") (pin "1") (pinfunction "1_1") (pintype "passive"))
      (node (ref "SW4") (pin "1") (pinfunction "1_1") (pintype "passive"))
    )
    (net (code "54") (name "Net-(R29-Pad1)") (class "Default")
      (node (ref "R29") (pin "1") (pinfunction "1_1") (pintype "passive"))
      (node (ref "SW5") (pin "1") (pinfunction "1_1") (pintype "passive"))
    )
    (net (code "55") (name "Net-(U2-EN)") (class "Default")
      (node (ref "C11") (pin "2") (pinfunction "2_2") (pintype "passive"))
      (node (ref "R3") (pin "2") (pinfunction "2_2") (pintype "passive"))
      (node (ref "U2") (pin "1") (pinfunction "EN_1") (pintype "passive"))
    )
    (net (code "56") (name "Net-(U2-FB)") (class "Default")
      (node (ref "C10") (pin "2") (pinfunction "2_2") (pintype "passive"))
      (node (ref "R1") (pin "2") (pinfunction "2_2") (pintype "passive"))
      (node (ref "R2") (pin "1") (pinfunction "1_1") (pintype "passive"))
      (node (ref "U2") (pin "5") (pinfunction "FB_5") (pintype "passive"))
    )
    (net (code "57") (name "Net-(U2-SW)") (class "Default")
      (node (ref "L2") (pin "1") (pinfunction "1_1") (pintype "passive"))
      (node (ref "U2") (pin "3") (pinfunction "SW_3") (pintype "passive"))
    )
    (net (code "58") (name "Net-(U3-C{slash}INT3{slash}P0.7)") (class "Default")
      (node (ref "C13") (pin "1") (pinfunction "1_1") (pintype "passive"))
      (node (ref "U3") (pin "1") (pinfunction "C/INT3/P0.7_1") (pintype "passive"))
    )
    (net (code "59") (name "Net-(U3-XTAL1{slash}TK16{slash}P5.0)") (class "Default")
      (node (ref "C16") (pin "1") (pinfunction "1_1") (pintype "passive"))
      (node (ref "R31") (pin "1") (pinfunction "1_1") (pintype "passive"))
      (node (ref "U3") (pin "3") (pinfunction "XTAL1/TK16/P5.0_3") (pintype "passive"))
      (node (ref "Y1") (pin "3") (pinfunction "X2_3") (pintype "passive"))
    )
    (net (code "60") (name "Net-(U3-XTAL2{slash}TK17{slash}P5.1)") (class "Default")
      (node (ref "C15") (pin "1") (pinfunction "1_1") (pintype "passive"))
      (node (ref "R31") (pin "2") (pinfunction "2_2") (pintype "passive"))
      (node (ref "U3") (pin "4") (pinfunction "XTAL2/TK17/P5.1_4") (pintype "passive"))
      (node (ref "Y1") (pin "1") (pinfunction "X1_1") (pintype "passive"))
    )
    (net (code "61") (name "UART_RX_0") (class "Default")
      (node (ref "R33") (pin "2") (pinfunction "2_2") (pintype "passive"))
    )
    (net (code "62") (name "UART_TX_0") (class "Default")
      (node (ref "R32") (pin "2") (pinfunction "2_2") (pintype "passive"))
    )
    (net (code "63") (name "VCC_5V") (class "Default")
      (node (ref "C3") (pin "1") (pinfunction "1_1") (pintype "passive"))
      (node (ref "CN1") (pin "1") (pinfunction "1_1") (pintype "passive"))
      (node (ref "CN3") (pin "1") (pinfunction "1_1") (pintype "passive"))
      (node (ref "EC3") (pin "1") (pinfunction "1_1") (pintype "passive"))
      (node (ref "R5") (pin "2") (pinfunction "2_2") (pintype "passive"))
      (node (ref "R6") (pin "2") (pinfunction "2_2") (pintype "passive"))
    )
    (net (code "64") (name "VDD3V3") (class "Default")
      (node (ref "C10") (pin "1") (pinfunction "1_1") (pintype "passive"))
      (node (ref "C12") (pin "2") (pinfunction "2_2") (pintype "passive"))
      (node (ref "C6") (pin "2") (pinfunction "2_2") (pintype "passive"))
      (node (ref "C7") (pin "2") (pinfunction "2_2") (pintype "passive"))
      (node (ref "C8") (pin "2") (pinfunction "2_2") (pintype "passive"))
      (node (ref "C9") (pin "2") (pinfunction "2_2") (pintype "passive"))
      (node (ref "L2") (pin "2") (pinfunction "2_2") (pintype "passive"))
      (node (ref "R11") (pin "1") (pinfunction "1_1") (pintype "passive"))
      (node (ref "R12") (pin "2") (pinfunction "2_2") (pintype "passive"))
      (node (ref "R14") (pin "1") (pinfunction "1_1") (pintype "passive"))
      (node (ref "R15") (pin "2") (pinfunction "2_2") (pintype "passive"))
      (node (ref "R2") (pin "2") (pinfunction "2_2") (pintype "passive"))
    )
    (net (code "65") (name "VDD5V") (class "Default")
      (node (ref "C17") (pin "2") (pinfunction "2_2") (pintype "passive"))
      (node (ref "C2") (pin "2") (pinfunction "2_2") (pintype "passive"))
      (node (ref "D1") (pin "2") (pinfunction "K_2") (pintype "passive"))
      (node (ref "J1") (pin "1") (pinfunction "1_1") (pintype "passive"))
      (node (ref "L1") (pin "2") (pinfunction "2_2") (pintype "passive"))
      (node (ref "LED6") (pin "1") (pinfunction "A_1") (pintype "passive"))
      (node (ref "R10") (pin "2") (pinfunction "2_2") (pintype "passive"))
      (node (ref "R13") (pin "2") (pinfunction "2_2") (pintype "passive"))
      (node (ref "R19") (pin "2") (pinfunction "2_2") (pintype "passive"))
      (node (ref "R20") (pin "2") (pinfunction "2_2") (pintype "passive"))
      (node (ref "R21") (pin "2") (pinfunction "2_2") (pintype "passive"))
      (node (ref "R3") (pin "1") (pinfunction "1_1") (pintype "passive"))
      (node (ref "R30") (pin "2") (pinfunction "2_2") (pintype "passive"))
      (node (ref "R84") (pin "1") (pinfunction "1_1") (pintype "passive"))
      (node (ref "R85") (pin "1") (pinfunction "1_1") (pintype "passive"))
      (node (ref "R86") (pin "1") (pinfunction "1_1") (pintype "passive"))
      (node (ref "R87") (pin "1") (pinfunction "1_1") (pintype "passive"))
      (node (ref "R88") (pin "1") (pinfunction "1_1") (pintype "passive"))
      (node (ref "U1") (pin "3") (pinfunction "FB_3") (pintype "passive"))
      (node (ref "U2") (pin "4") (pinfunction "VIN_4") (pintype "passive"))
      (node (ref "U3") (pin "6") (pinfunction "VDD_6") (pintype "passive"))
    )
  )
)
